# 07_FE_SWITCHING.net
KiCad netlist of a schematic drawn in Altium Designer
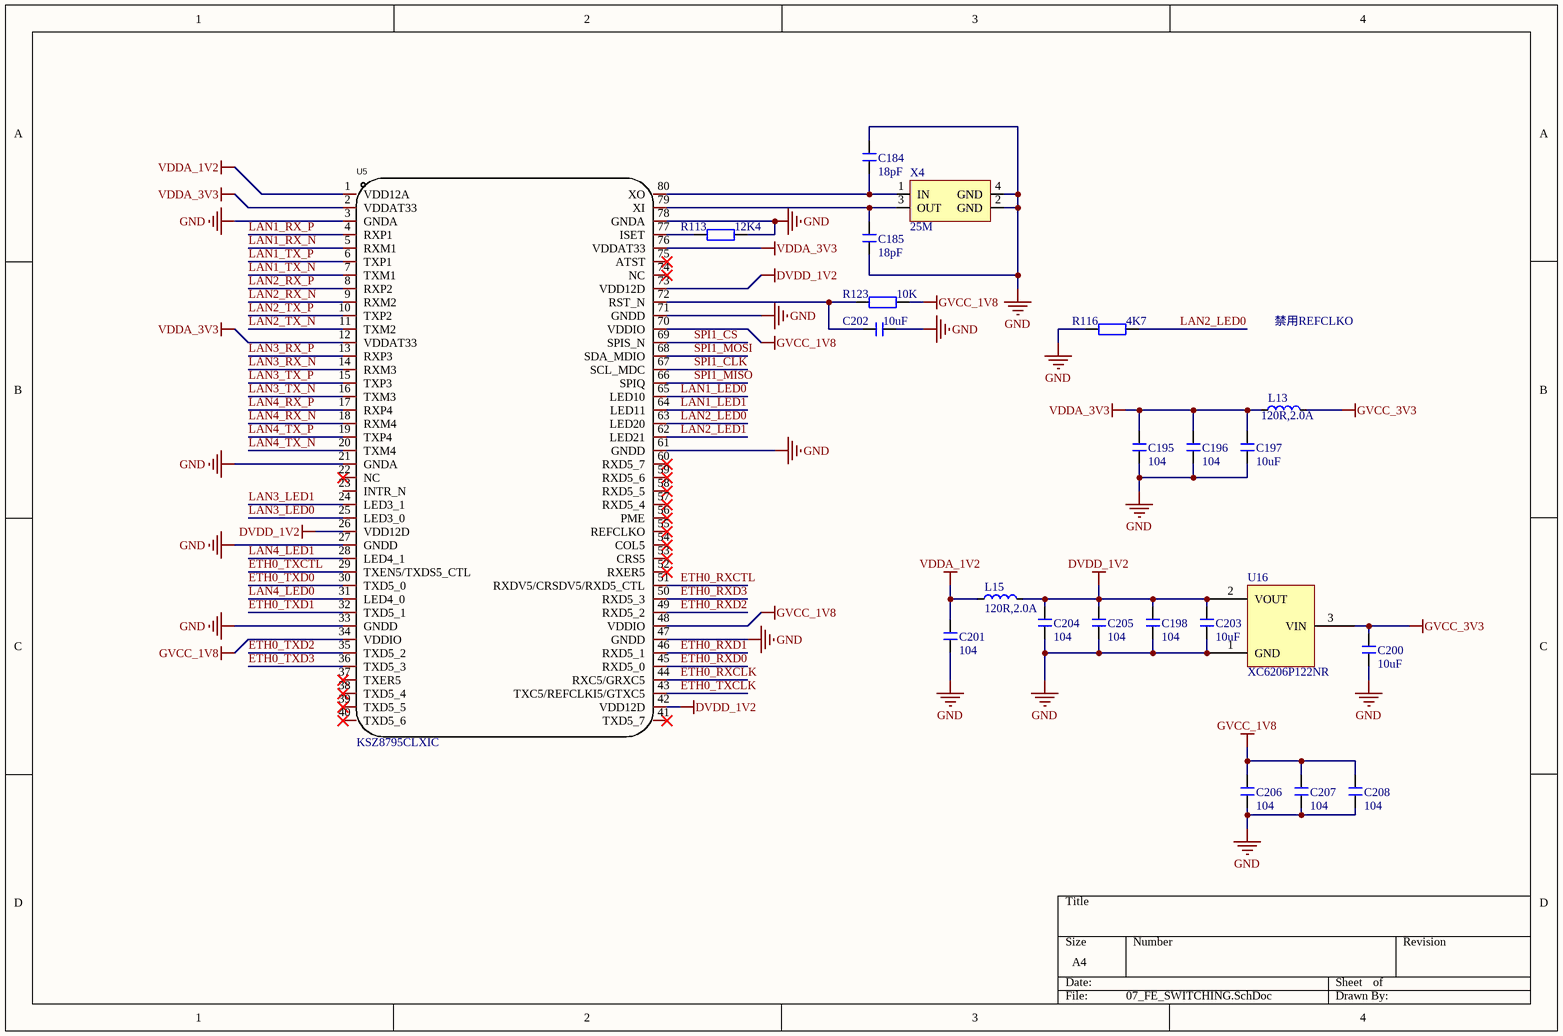
[diagram p0: 07_FE_SWITCHING.SchDoc]

(export (version "E")
  (design (tool "Eeschema 10.0.6"))
  (components
    (comp (ref "C184")
      (value "18pF")
      (footprint "C 0603")
      (description "无极性贴片电容")
      (fields (field (name "版权归属") "源创客"))
      (libsource (lib "STM32MP15x底板封装库V1.4") (part "C"))
    )
    (comp (ref "C185")
      (value "18pF")
      (footprint "C 0603")
      (description "无极性贴片电容")
      (fields (field (name "版权归属") "源创客"))
      (libsource (lib "STM32MP15x底板封装库V1.4") (part "C"))
    )
    (comp (ref "C195")
      (value "104")
      (footprint "C 0603")
      (description "无极性贴片电容")
      (fields (field (name "版权归属") "源创客"))
      (libsource (lib "STM32MP15x底板封装库V1.4") (part "C"))
    )
    (comp (ref "C196")
      (value "104")
      (footprint "C 0603")
      (description "无极性贴片电容")
      (fields (field (name "版权归属") "源创客"))
      (libsource (lib "STM32MP15x底板封装库V1.4") (part "C"))
    )
    (comp (ref "C197")
      (value "10uF")
      (footprint "C 0603")
      (description "无极性贴片电容")
      (fields (field (name "版权归属") "源创客"))
      (libsource (lib "STM32MP15x底板封装库V1.4") (part "C"))
    )
    (comp (ref "C198")
      (value "104")
      (footprint "C 0603")
      (description "无极性贴片电容")
      (fields (field (name "版权归属") "源创客"))
      (libsource (lib "STM32MP15x底板封装库V1.4") (part "C"))
    )
    (comp (ref "C200")
      (value "10uF")
      (footprint "C 0603")
      (description "无极性贴片电容")
      (fields (field (name "版权归属") "源创客"))
      (libsource (lib "STM32MP15x底板封装库V1.4") (part "C"))
    )
    (comp (ref "C201")
      (value "104")
      (footprint "C 0603")
      (description "无极性贴片电容")
      (fields (field (name "版权归属") "源创客"))
      (libsource (lib "STM32MP15x底板封装库V1.4") (part "C"))
    )
    (comp (ref "C202")
      (value "10uF")
      (footprint "C 0603")
      (description "无极性贴片电容")
      (fields (field (name "版权归属") "源创客"))
      (libsource (lib "STM32MP15x底板封装库V1.4") (part "C"))
    )
    (comp (ref "C203")
      (value "10uF")
      (footprint "C 0603")
      (description "无极性贴片电容")
      (fields (field (name "版权归属") "源创客"))
      (libsource (lib "STM32MP15x底板封装库V1.4") (part "C"))
    )
    (comp (ref "C204")
      (value "104")
      (footprint "C 0603")
      (description "无极性贴片电容")
      (fields (field (name "版权归属") "源创客"))
      (libsource (lib "STM32MP15x底板封装库V1.4") (part "C"))
    )
    (comp (ref "C205")
      (value "104")
      (footprint "C 0603")
      (description "无极性贴片电容")
      (fields (field (name "版权归属") "源创客"))
      (libsource (lib "STM32MP15x底板封装库V1.4") (part "C"))
    )
    (comp (ref "C206")
      (value "104")
      (footprint "C 0603")
      (description "无极性贴片电容")
      (fields (field (name "版权归属") "源创客"))
      (libsource (lib "STM32MP15x底板封装库V1.4") (part "C"))
    )
    (comp (ref "C207")
      (value "104")
      (footprint "C 0603")
      (description "无极性贴片电容")
      (fields (field (name "版权归属") "源创客"))
      (libsource (lib "STM32MP15x底板封装库V1.4") (part "C"))
    )
    (comp (ref "C208")
      (value "104")
      (footprint "C 0603")
      (description "无极性贴片电容")
      (fields (field (name "版权归属") "源创客"))
      (libsource (lib "STM32MP15x底板封装库V1.4") (part "C"))
    )
    (comp (ref "L13")
      (value "120R,2.0A")
      (footprint "L 0603")
      (description "小功率贴片电感磁珠")
      (fields (field (name "版权归属") "源创客"))
      (libsource (lib "STM32MP15x底板封装库V1.4") (part "L"))
    )
    (comp (ref "L15")
      (value "120R,2.0A")
      (footprint "L 0603")
      (description "小功率贴片电感磁珠")
      (fields (field (name "版权归属") "源创客"))
      (libsource (lib "STM32MP15x底板封装库V1.4") (part "L"))
    )
    (comp (ref "R113")
      (value "12K4")
      (footprint "R 0603")
      (description "贴片电阻")
      (fields (field (name "版权归属") "源创客"))
      (libsource (lib "STM32MP15x底板封装库V1.4") (part "R"))
    )
    (comp (ref "R116")
      (value "4K7")
      (footprint "R 0603")
      (description "贴片电阻")
      (fields (field (name "版权归属") "源创客"))
      (libsource (lib "STM32MP15x底板封装库V1.4") (part "R"))
    )
    (comp (ref "R123")
      (value "10K")
      (footprint "R 0603")
      (description "贴片电阻")
      (fields (field (name "版权归属") "源创客"))
      (libsource (lib "STM32MP15x底板封装库V1.4") (part "R"))
    )
    (comp (ref "U5")
      (value "KSZ8795CLXIC")
      (footprint "LQFP80_10x10")
      (fields (field (name "MANUFACTURER") "MICROCHIP(美国微芯)"))
      (libsource (lib "KSZ8795CLXIC") (part "KSZ8795CLXIC"))
    )
    (comp (ref "U16")
      (value "XC6206P122NR")
      (footprint "SOT23-3M")
      (libsource (lib "XC6206-1.8NR") (part "XC6206-1.8NR"))
    )
    (comp (ref "X4")
      (value "25M")
      (footprint "XTAL-3225")
      (description "4脚无源晶振")
      (fields (field (name "版权归属") "源创客"))
      (libsource (lib "STM32MP15x底板封装库V1.4") (part "XTAL-4P"))
    )
  )
  (nets
    (net (code "1") (name "/ETH0_RXCLK") (class "Default")
      (node (ref "U5") (pin "44") (pinfunction "RXC5/GRXC5_44") (pintype "passive"))
    )
    (net (code "2") (name "/ETH0_RXCTL") (class "Default")
      (node (ref "U5") (pin "51") (pinfunction "RXDV5/CRSDV5/RXD5_CTL_51") (pintype "passive"))
    )
    (net (code "3") (name "/ETH0_RXD0") (class "Default")
      (node (ref "U5") (pin "45") (pinfunction "RXD5_0_45") (pintype "passive"))
    )
    (net (code "4") (name "/ETH0_RXD1") (class "Default")
      (node (ref "U5") (pin "46") (pinfunction "RXD5_1_46") (pintype "passive"))
    )
    (net (code "5") (name "/ETH0_RXD2") (class "Default")
      (node (ref "U5") (pin "49") (pinfunction "RXD5_2_49") (pintype "passive"))
    )
    (net (code "6") (name "/ETH0_RXD3") (class "Default")
      (node (ref "U5") (pin "50") (pinfunction "RXD5_3_50") (pintype "passive"))
    )
    (net (code "7") (name "/ETH0_TXCLK") (class "Default")
      (node (ref "U5") (pin "43") (pinfunction "TXC5/REFCLKI5/GTXC5_43") (pintype "passive"))
    )
    (net (code "8") (name "/ETH0_TXCTL") (class "Default")
      (node (ref "U5") (pin "29") (pinfunction "TXEN5/TXDS5_CTL_29") (pintype "passive"))
    )
    (net (code "9") (name "/ETH0_TXD0") (class "Default")
      (node (ref "U5") (pin "30") (pinfunction "TXD5_0_30") (pintype "passive"))
    )
    (net (code "10") (name "/ETH0_TXD1") (class "Default")
      (node (ref "U5") (pin "32") (pinfunction "TXD5_1_32") (pintype "passive"))
    )
    (net (code "11") (name "/ETH0_TXD2") (class "Default")
      (node (ref "U5") (pin "35") (pinfunction "TXD5_2_35") (pintype "passive"))
    )
    (net (code "12") (name "/ETH0_TXD3") (class "Default")
      (node (ref "U5") (pin "36") (pinfunction "TXD5_3_36") (pintype "passive"))
    )
    (net (code "13") (name "/LAN1_LED0") (class "Default")
      (node (ref "U5") (pin "65") (pinfunction "LED10_65") (pintype "passive"))
    )
    (net (code "14") (name "/LAN1_LED1") (class "Default")
      (node (ref "U5") (pin "64") (pinfunction "LED11_64") (pintype "passive"))
    )
    (net (code "15") (name "/LAN1_RX_N") (class "Default")
      (node (ref "U5") (pin "5") (pinfunction "RXM1_5") (pintype "passive"))
    )
    (net (code "16") (name "/LAN1_RX_P") (class "Default")
      (node (ref "U5") (pin "4") (pinfunction "RXP1_4") (pintype "passive"))
    )
    (net (code "17") (name "/LAN1_TX_N") (class "Default")
      (node (ref "U5") (pin "7") (pinfunction "TXM1_7") (pintype "passive"))
    )
    (net (code "18") (name "/LAN1_TX_P") (class "Default")
      (node (ref "U5") (pin "6") (pinfunction "TXP1_6") (pintype "passive"))
    )
    (net (code "19") (name "/LAN2_LED0") (class "Default")
      (node (ref "R116") (pin "2") (pinfunction "2_2") (pintype "passive"))
      (node (ref "U5") (pin "63") (pinfunction "LED20_63") (pintype "passive"))
    )
    (net (code "20") (name "/LAN2_LED1") (class "Default")
      (node (ref "U5") (pin "62") (pinfunction "LED21_62") (pintype "passive"))
    )
    (net (code "21") (name "/LAN2_RX_N") (class "Default")
      (node (ref "U5") (pin "9") (pinfunction "RXM2_9") (pintype "passive"))
    )
    (net (code "22") (name "/LAN2_RX_P") (class "Default")
      (node (ref "U5") (pin "8") (pinfunction "RXP2_8") (pintype "passive"))
    )
    (net (code "23") (name "/LAN2_TX_N") (class "Default")
      (node (ref "U5") (pin "11") (pinfunction "TXM2_11") (pintype "passive"))
    )
    (net (code "24") (name "/LAN2_TX_P") (class "Default")
      (node (ref "U5") (pin "10") (pinfunction "TXP2_10") (pintype "passive"))
    )
    (net (code "25") (name "/LAN3_LED0") (class "Default")
      (node (ref "U5") (pin "25") (pinfunction "LED3_0_25") (pintype "passive"))
    )
    (net (code "26") (name "/LAN3_LED1") (class "Default")
      (node (ref "U5") (pin "24") (pinfunction "LED3_1_24") (pintype "passive"))
    )
    (net (code "27") (name "/LAN3_RX_N") (class "Default")
      (node (ref "U5") (pin "14") (pinfunction "RXM3_14") (pintype "passive"))
    )
    (net (code "28") (name "/LAN3_RX_P") (class "Default")
      (node (ref "U5") (pin "13") (pinfunction "RXP3_13") (pintype "passive"))
    )
    (net (code "29") (name "/LAN3_TX_N") (class "Default")
      (node (ref "U5") (pin "16") (pinfunction "TXM3_16") (pintype "passive"))
    )
    (net (code "30") (name "/LAN3_TX_P") (class "Default")
      (node (ref "U5") (pin "15") (pinfunction "TXP3_15") (pintype "passive"))
    )
    (net (code "31") (name "/LAN4_LED0") (class "Default")
      (node (ref "U5") (pin "31") (pinfunction "LED4_0_31") (pintype "passive"))
    )
    (net (code "32") (name "/LAN4_LED1") (class "Default")
      (node (ref "U5") (pin "28") (pinfunction "LED4_1_28") (pintype "passive"))
    )
    (net (code "33") (name "/LAN4_RX_N") (class "Default")
      (node (ref "U5") (pin "18") (pinfunction "RXM4_18") (pintype "passive"))
    )
    (net (code "34") (name "/LAN4_RX_P") (class "Default")
      (node (ref "U5") (pin "17") (pinfunction "RXP4_17") (pintype "passive"))
    )
    (net (code "35") (name "/LAN4_TX_N") (class "Default")
      (node (ref "U5") (pin "20") (pinfunction "TXM4_20") (pintype "passive"))
    )
    (net (code "36") (name "/LAN4_TX_P") (class "Default")
      (node (ref "U5") (pin "19") (pinfunction "TXP4_19") (pintype "passive"))
    )
    (net (code "37") (name "/SPI1_CLK") (class "Default")
      (node (ref "U5") (pin "67") (pinfunction "SCL_MDC_67") (pintype "passive"))
    )
    (net (code "38") (name "/SPI1_CS") (class "Default")
      (node (ref "U5") (pin "69") (pinfunction "SPIS_N_69") (pintype "passive"))
    )
    (net (code "39") (name "/SPI1_MISO") (class "Default")
      (node (ref "U5") (pin "66") (pinfunction "SPIQ_66") (pintype "passive"))
    )
    (net (code "40") (name "/SPI1_MOSI") (class "Default")
      (node (ref "U5") (pin "68") (pinfunction "SDA_MDIO_68") (pintype "passive"))
    )
    (net (code "41") (name "DVDD_1V2") (class "Default")
      (node (ref "C198") (pin "2") (pinfunction "2_2") (pintype "passive"))
      (node (ref "C203") (pin "2") (pinfunction "2_2") (pintype "passive"))
      (node (ref "C204") (pin "2") (pinfunction "2_2") (pintype "passive"))
      (node (ref "C205") (pin "2") (pinfunction "2_2") (pintype "passive"))
      (node (ref "L15") (pin "2") (pinfunction "2_2") (pintype "passive"))
      (node (ref "U16") (pin "2") (pinfunction "VOUT_2") (pintype "passive"))
      (node (ref "U5") (pin "26") (pinfunction "VDD12D_26") (pintype "passive"))
      (node (ref "U5") (pin "42") (pinfunction "VDD12D_42") (pintype "passive"))
      (node (ref "U5") (pin "73") (pinfunction "VDD12D_73") (pintype "passive"))
    )
    (net (code "42") (name "GND") (class "Default")
      (node (ref "C184") (pin "2") (pinfunction "2_2") (pintype "passive"))
      (node (ref "C185") (pin "1") (pinfunction "1_1") (pintype "passive"))
      (node (ref "C195") (pin "1") (pinfunction "1_1") (pintype "passive"))
      (node (ref "C196") (pin "1") (pinfunction "1_1") (pintype "passive"))
      (node (ref "C197") (pin "1") (pinfunction "1_1") (pintype "passive"))
      (node (ref "C198") (pin "1") (pinfunction "1_1") (pintype "passive"))
      (node (ref "C200") (pin "1") (pinfunction "1_1") (pintype "passive"))
      (node (ref "C201") (pin "1") (pinfunction "1_1") (pintype "passive"))
      (node (ref "C202") (pin "1") (pinfunction "1_1") (pintype "passive"))
      (node (ref "C203") (pin "1") (pinfunction "1_1") (pintype "passive"))
      (node (ref "C204") (pin "1") (pinfunction "1_1") (pintype "passive"))
      (node (ref "C205") (pin "1") (pinfunction "1_1") (pintype "passive"))
      (node (ref "C206") (pin "1") (pinfunction "1_1") (pintype "passive"))
      (node (ref "C207") (pin "1") (pinfunction "1_1") (pintype "passive"))
      (node (ref "C208") (pin "1") (pinfunction "1_1") (pintype "passive"))
      (node (ref "R113") (pin "2") (pinfunction "2_2") (pintype "passive"))
      (node (ref "R116") (pin "1") (pinfunction "1_1") (pintype "passive"))
      (node (ref "U16") (pin "1") (pinfunction "GND_1") (pintype "passive"))
      (node (ref "U5") (pin "21") (pinfunction "GNDA_21") (pintype "passive"))
      (node (ref "U5") (pin "27") (pinfunction "GNDD_27") (pintype "passive"))
      (node (ref "U5") (pin "3") (pinfunction "GNDA_3") (pintype "passive"))
      (node (ref "U5") (pin "33") (pinfunction "GNDD_33") (pintype "passive"))
      (node (ref "U5") (pin "47") (pinfunction "GNDD_47") (pintype "passive"))
      (node (ref "U5") (pin "61") (pinfunction "GNDD_61") (pintype "passive"))
      (node (ref "U5") (pin "71") (pinfunction "GNDD_71") (pintype "passive"))
      (node (ref "U5") (pin "78") (pinfunction "GNDA_78") (pintype "passive"))
      (node (ref "X4") (pin "2") (pinfunction "GND_2") (pintype "passive"))
      (node (ref "X4") (pin "4") (pinfunction "GND_4") (pintype "passive"))
    )
    (net (code "43") (name "GVCC_1V8") (class "Default")
      (node (ref "C206") (pin "2") (pinfunction "2_2") (pintype "passive"))
      (node (ref "C207") (pin "2") (pinfunction "2_2") (pintype "passive"))
      (node (ref "C208") (pin "2") (pinfunction "2_2") (pintype "passive"))
      (node (ref "R123") (pin "2") (pinfunction "2_2") (pintype "passive"))
      (node (ref "U5") (pin "34") (pinfunction "VDDIO_34") (pintype "passive"))
      (node (ref "U5") (pin "48") (pinfunction "VDDIO_48") (pintype "passive"))
      (node (ref "U5") (pin "70") (pinfunction "VDDIO_70") (pintype "passive"))
    )
    (net (code "44") (name "GVCC_3V3") (class "Default")
      (node (ref "C200") (pin "2") (pinfunction "2_2") (pintype "passive"))
      (node (ref "L13") (pin "2") (pinfunction "2_2") (pintype "passive"))
      (node (ref "U16") (pin "3") (pinfunction "VIN_3") (pintype "passive"))
    )
    (net (code "45") (name "Net-(U5-ISET)") (class "Default")
      (node (ref "R113") (pin "1") (pinfunction "1_1") (pintype "passive"))
      (node (ref "U5") (pin "77") (pinfunction "ISET_77") (pintype "passive"))
    )
    (net (code "46") (name "Net-(U5-RST_N)") (class "Default")
      (node (ref "C202") (pin "2") (pinfunction "2_2") (pintype "passive"))
      (node (ref "R123") (pin "1") (pinfunction "1_1") (pintype "passive"))
      (node (ref "U5") (pin "72") (pinfunction "RST_N_72") (pintype "passive"))
    )
    (net (code "47") (name "Net-(U5-XI)") (class "Default")
      (node (ref "C185") (pin "2") (pinfunction "2_2") (pintype "passive"))
      (node (ref "U5") (pin "79") (pinfunction "XI_79") (pintype "passive"))
      (node (ref "X4") (pin "3") (pinfunction "OUT_3") (pintype "passive"))
    )
    (net (code "48") (name "Net-(U5-XO)") (class "Default")
      (node (ref "C184") (pin "1") (pinfunction "1_1") (pintype "passive"))
      (node (ref "U5") (pin "80") (pinfunction "XO_80") (pintype "passive"))
      (node (ref "X4") (pin "1") (pinfunction "IN_1") (pintype "passive"))
    )
    (net (code "49") (name "VDDA_1V2") (class "Default")
      (node (ref "C201") (pin "2") (pinfunction "2_2") (pintype "passive"))
      (node (ref "L15") (pin "1") (pinfunction "1_1") (pintype "passive"))
      (node (ref "U5") (pin "1") (pinfunction "VDD12A_1") (pintype "passive"))
    )
    (net (code "50") (name "VDDA_3V3") (class "Default")
      (node (ref "C195") (pin "2") (pinfunction "2_2") (pintype "passive"))
      (node (ref "C196") (pin "2") (pinfunction "2_2") (pintype "passive"))
      (node (ref "C197") (pin "2") (pinfunction "2_2") (pintype "passive"))
      (node (ref "L13") (pin "1") (pinfunction "1_1") (pintype "passive"))
      (node (ref "U5") (pin "12") (pinfunction "VDDAT33_12") (pintype "passive"))
      (node (ref "U5") (pin "2") (pinfunction "VDDAT33_2") (pintype "passive"))
      (node (ref "U5") (pin "76") (pinfunction "VDDAT33_76") (pintype "passive"))
    )
    (net (code "51") (name "unconnected-(U5-ATST-Pad75)") (class "Default")
      (node (ref "U5") (pin "75") (pinfunction "ATST_75") (pintype "passive+no_connect"))
    )
    (net (code "52") (name "unconnected-(U5-COL5-Pad54)") (class "Default")
      (node (ref "U5") (pin "54") (pinfunction "COL5_54") (pintype "passive+no_connect"))
    )
    (net (code "53") (name "unconnected-(U5-CRS5-Pad53)") (class "Default")
      (node (ref "U5") (pin "53") (pinfunction "CRS5_53") (pintype "passive+no_connect"))
    )
    (net (code "54") (name "unconnected-(U5-INTR_N-Pad23)") (class "Default")
      (node (ref "U5") (pin "23") (pinfunction "INTR_N_23") (pintype "passive"))
    )
    (net (code "55") (name "unconnected-(U5-NC-Pad22)") (class "Default")
      (node (ref "U5") (pin "22") (pinfunction "NC_22") (pintype "passive+no_connect"))
    )
    (net (code "56") (name "unconnected-(U5-NC-Pad74)") (class "Default")
      (node (ref "U5") (pin "74") (pinfunction "NC_74") (pintype "passive+no_connect"))
    )
    (net (code "57") (name "unconnected-(U5-PME-Pad56)") (class "Default")
      (node (ref "U5") (pin "56") (pinfunction "PME_56") (pintype "passive+no_connect"))
    )
    (net (code "58") (name "unconnected-(U5-REFCLKO-Pad55)") (class "Default")
      (node (ref "U5") (pin "55") (pinfunction "REFCLKO_55") (pintype "passive+no_connect"))
    )
    (net (code "59") (name "unconnected-(U5-RXD5_4-Pad57)") (class "Default")
      (node (ref "U5") (pin "57") (pinfunction "RXD5_4_57") (pintype "passive+no_connect"))
    )
    (net (code "60") (name "unconnected-(U5-RXD5_5-Pad58)") (class "Default")
      (node (ref "U5") (pin "58") (pinfunction "RXD5_5_58") (pintype "passive+no_connect"))
    )
    (net (code "61") (name "unconnected-(U5-RXD5_6-Pad59)") (class "Default")
      (node (ref "U5") (pin "59") (pinfunction "RXD5_6_59") (pintype "passive+no_connect"))
    )
    (net (code "62") (name "unconnected-(U5-RXD5_7-Pad60)") (class "Default")
      (node (ref "U5") (pin "60") (pinfunction "RXD5_7_60") (pintype "passive+no_connect"))
    )
    (net (code "63") (name "unconnected-(U5-RXER5-Pad52)") (class "Default")
      (node (ref "U5") (pin "52") (pinfunction "RXER5_52") (pintype "passive+no_connect"))
    )
    (net (code "64") (name "unconnected-(U5-TXD5_4-Pad38)") (class "Default")
      (node (ref "U5") (pin "38") (pinfunction "TXD5_4_38") (pintype "passive+no_connect"))
    )
    (net (code "65") (name "unconnected-(U5-TXD5_5-Pad39)") (class "Default")
      (node (ref "U5") (pin "39") (pinfunction "TXD5_5_39") (pintype "passive+no_connect"))
    )
    (net (code "66") (name "unconnected-(U5-TXD5_6-Pad40)") (class "Default")
      (node (ref "U5") (pin "40") (pinfunction "TXD5_6_40") (pintype "passive+no_connect"))
    )
    (net (code "67") (name "unconnected-(U5-TXD5_7-Pad41)") (class "Default")
      (node (ref "U5") (pin "41") (pinfunction "TXD5_7_41") (pintype "passive+no_connect"))
    )
    (net (code "68") (name "unconnected-(U5-TXER5-Pad37)") (class "Default")
      (node (ref "U5") (pin "37") (pinfunction "TXER5_37") (pintype "passive+no_connect"))
    )
  )
)
